# Micro_Grid_Sch.net
KiCad netlist of a schematic drawn in Altium Designer
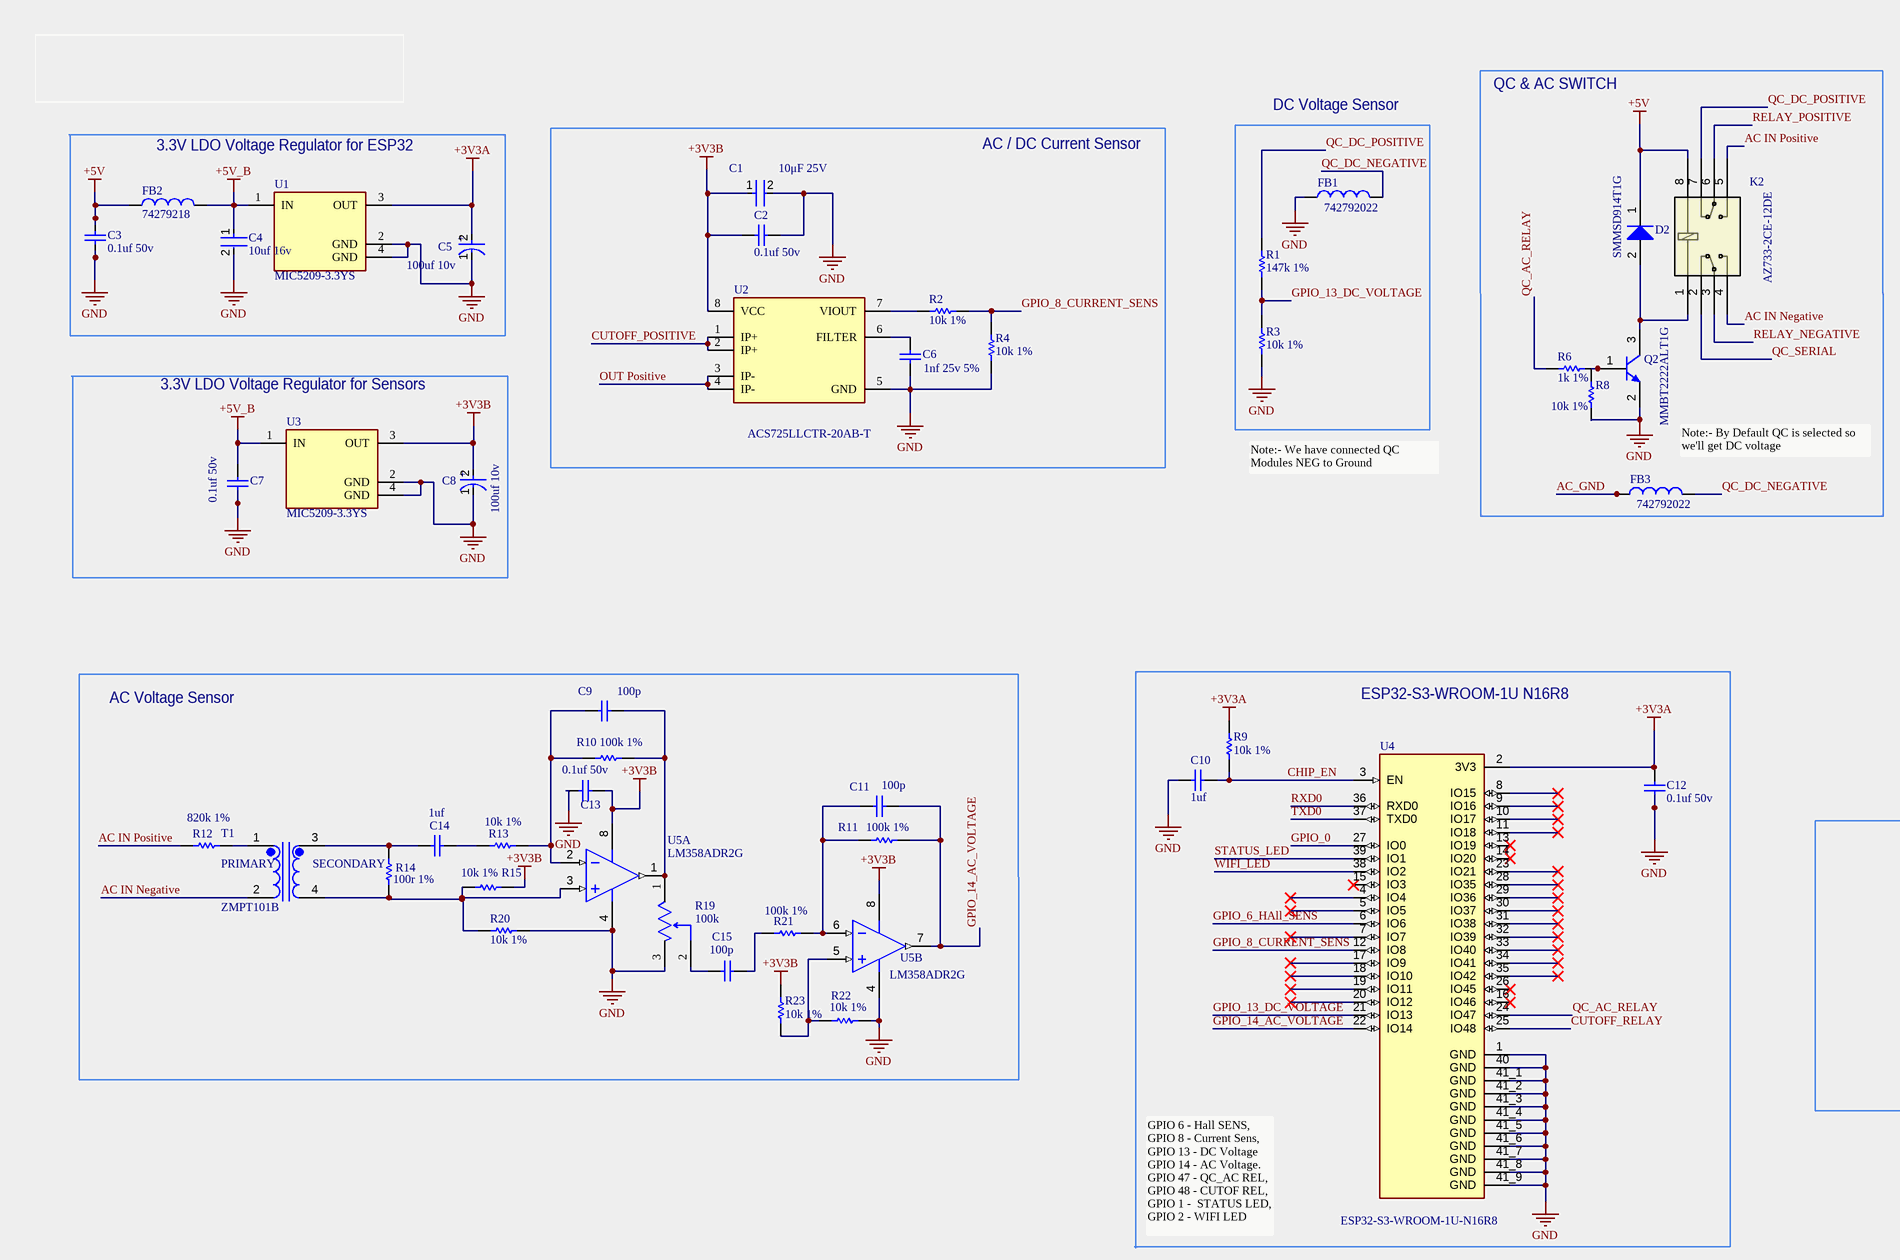
[diagram p0: Micro_Grid_Sch.SchDoc, top left]
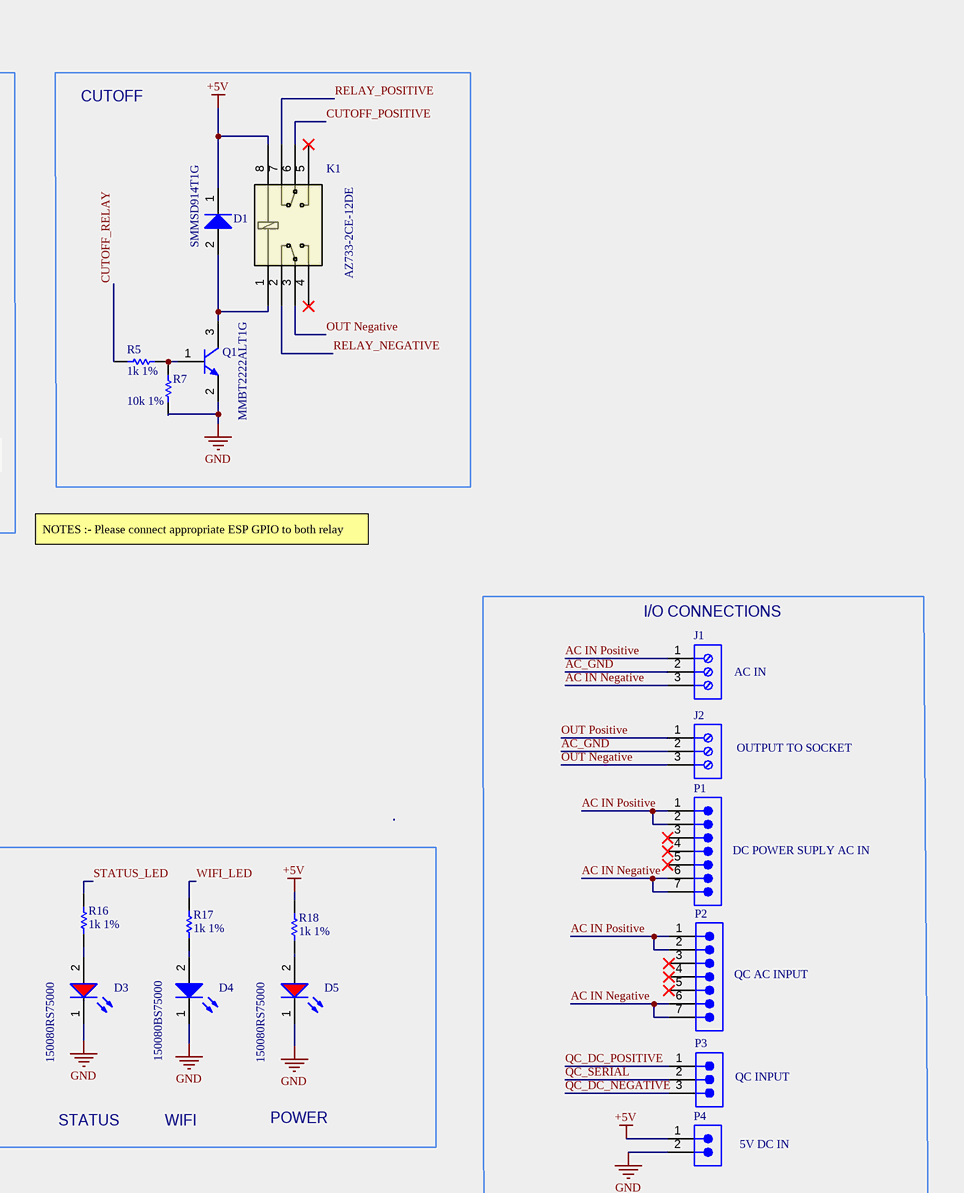
[diagram p1: Micro_Grid_Sch.SchDoc, top right]
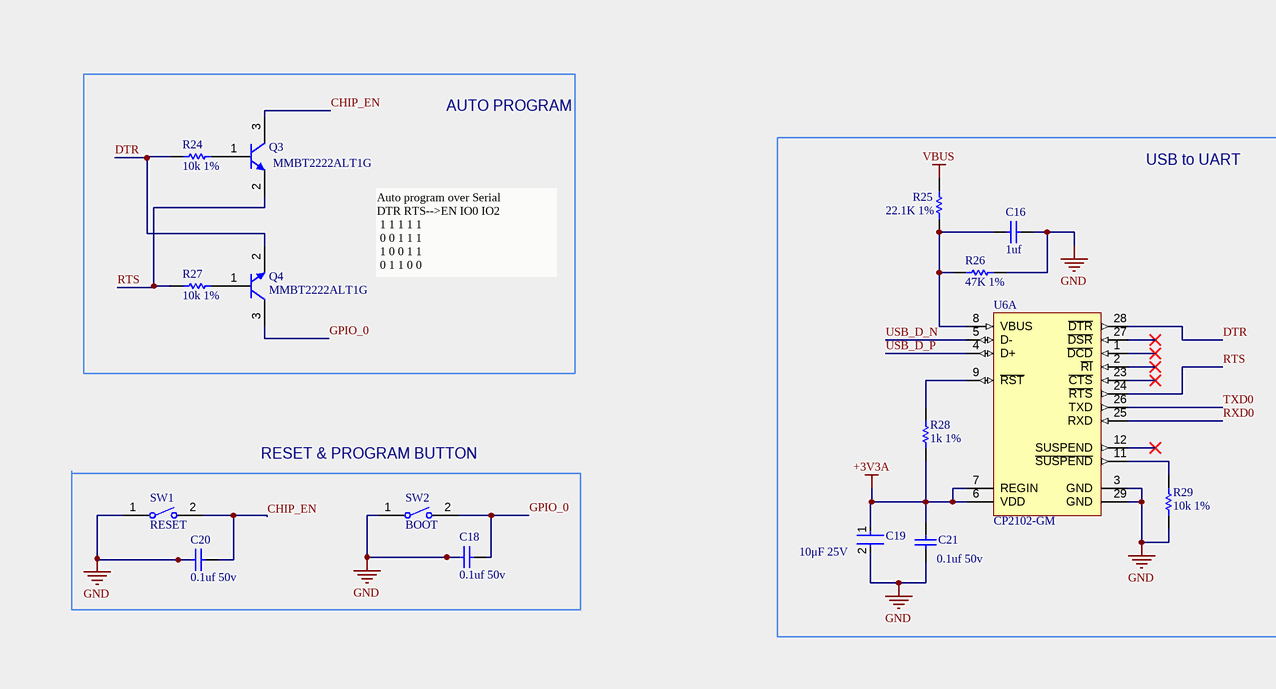
[diagram p2: Micro_Grid_Sch.SchDoc, bottom left]
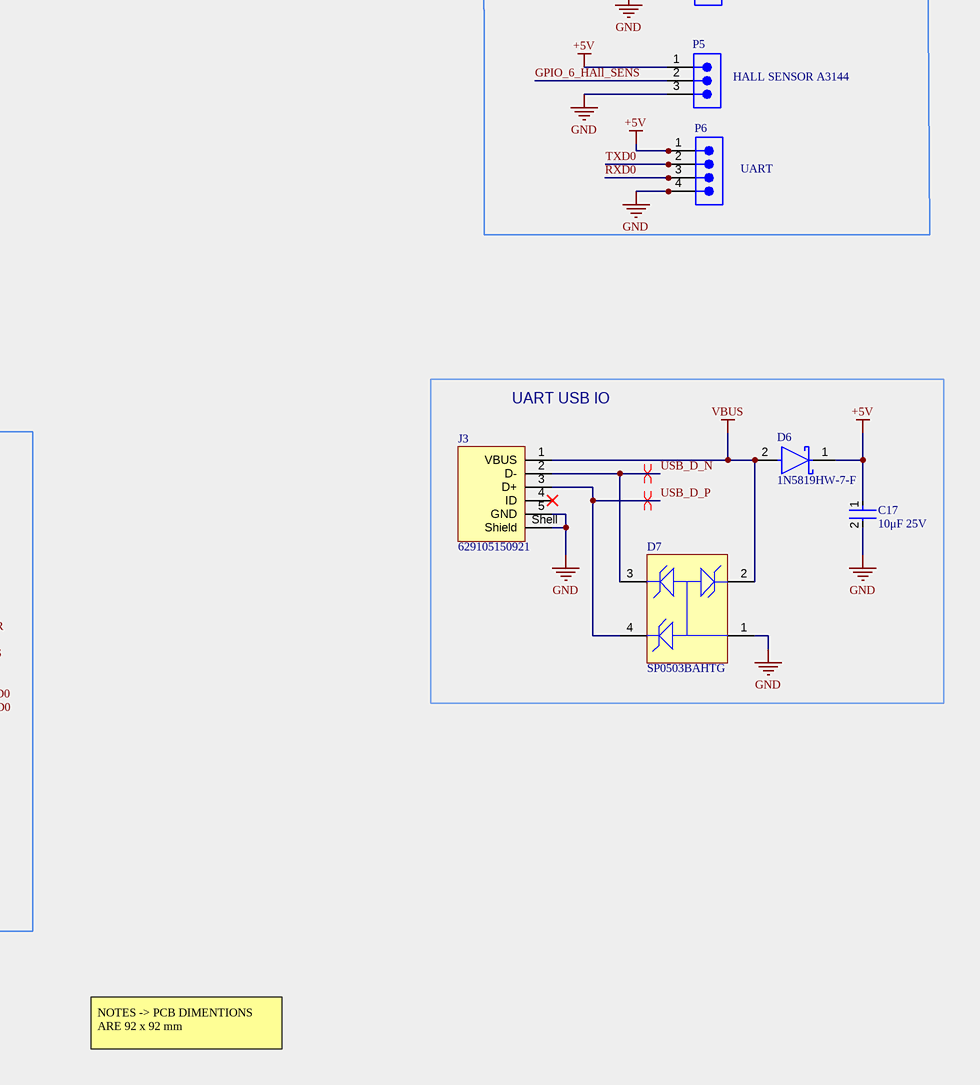
[diagram p3: Micro_Grid_Sch.SchDoc, bottom right]

(export (version "E")
  (design (tool "Eeschema 10.0.6"))
  (components
    (comp (ref "C1")
      (value "10μF 25V")
      (footprint "FP-C2012-125-0_2-IPC_B")
      (description "Multilayer Ceramic Capacitors 10μF ±10% 25V X5R SMD 0805")
      (fields (field (name "VOLTAGE") "25V") (field (name "TOLERANCE") "10%"))
      (libsource (lib "Altium Content Vault") (part "b4654b650e69147ec39a6b967a45e02"))
    )
    (comp (ref "C2")
      (value "0.1uf 50v")
      (footprint "CAPC2013X140X50LL20T25")
      (description "08055F104KAT2A")
      (fields (field (name "MANUFACTURER") "AVX Interconnect / Elco"))
      (libsource (lib "Altium Content Vault") (part "CAP"))
    )
    (comp (ref "C3")
      (value "0.1uf 50v")
      (footprint "CAPC2013X140X50LL20T25")
      (description "08055F104KAT2A")
      (fields (field (name "MANUFACTURER") "AVX Interconnect / Elco"))
      (libsource (lib "Altium Content Vault") (part "CAP"))
    )
    (comp (ref "C4")
      (value "10uf 16v")
      (footprint "FP-GRM21B-0_1-IPC_C")
      (description "Chip Multilayer Ceramic Capacitors for General Purpose, 0805, 10uF, X5R, 15%, 10%, 16V")
      (fields (field (name "TOLERANCE") "10%") (field (name "VOLTAGE") "16V"))
      (libsource (lib "Altium Content Vault") (part "b4654b650e69147ec39a6b967a45e02"))
    )
    (comp (ref "C5")
      (value "100uf 10v")
      (footprint "FP-SC-MFG")
      (description "EEE-1AA101WR, CAP ALUM 100UF 20% 10V SMD")
      (fields (field (name "TOLERANCE") "20%"))
      (libsource (lib "Altium Content Vault") (part "a00bbbee19879c290e62620ae7e47b1"))
    )
    (comp (ref "C6")
      (value "1nf 25v 5%")
      (footprint "CAPC2013X145X50NL20T20")
      (description "VJ0805Y102JXXPW1BC")
      (fields (field (name "MANUFACTURER") "Vitramon"))
      (libsource (lib "Altium Content Vault") (part "CAP"))
    )
    (comp (ref "C7")
      (value "0.1uf 50v")
      (footprint "CAPC2013X140X50LL20T25")
      (description "08055F104KAT2A")
      (fields (field (name "MANUFACTURER") "AVX Interconnect / Elco"))
      (libsource (lib "Altium Content Vault") (part "CAP"))
    )
    (comp (ref "C8")
      (value "100uf 10v")
      (footprint "FP-SC-MFG")
      (description "EEE-1AA101WR, CAP ALUM 100UF 20% 10V SMD")
      (fields (field (name "TOLERANCE") "20%"))
      (libsource (lib "Altium Content Vault") (part "a00bbbee19879c290e62620ae7e47b1"))
    )
    (comp (ref "C9")
      (value "100p")
      (footprint "CAPC2013X140X50NL20T25")
      (description "C0805C101KCGACTU")
      (fields (field (name "MANUFACTURER") "Kemet"))
      (libsource (lib "Altium Content Vault") (part "CAP"))
    )
    (comp (ref "C10")
      (value "1uf")
      (footprint "CAPC2013X140X50LL20T25")
      (description "C0805C105K3RACTU")
      (fields (field (name "MANUFACTURER") "Kemet"))
      (libsource (lib "Altium Content Vault") (part "CAP"))
    )
    (comp (ref "C11")
      (value "100p")
      (footprint "CAPC2013X140X50NL20T25")
      (description "C0805C101KCGACTU")
      (fields (field (name "MANUFACTURER") "Kemet"))
      (libsource (lib "Altium Content Vault") (part "CAP"))
    )
    (comp (ref "C12")
      (value "0.1uf 50v")
      (footprint "CAPC2013X140X50LL20T25")
      (description "08055F104KAT2A")
      (fields (field (name "MANUFACTURER") "AVX Interconnect / Elco"))
      (libsource (lib "Altium Content Vault") (part "CAP"))
    )
    (comp (ref "C13")
      (value "0.1uf 50v")
      (footprint "CAPC2013X140X50LL20T25")
      (description "08055F104KAT2A")
      (fields (field (name "MANUFACTURER") "AVX Interconnect / Elco"))
      (libsource (lib "Altium Content Vault") (part "CAP"))
    )
    (comp (ref "C14")
      (value "1uf")
      (footprint "CAPC2013X140X50LL20T25")
      (description "C0805C105K3RACTU")
      (fields (field (name "MANUFACTURER") "Kemet"))
      (libsource (lib "Altium Content Vault") (part "CAP"))
    )
    (comp (ref "C15")
      (value "100p")
      (footprint "CAPC2013X140X50NL20T25")
      (description "C0805C101KCGACTU")
      (fields (field (name "MANUFACTURER") "Kemet"))
      (libsource (lib "Altium Content Vault") (part "CAP"))
    )
    (comp (ref "C16")
      (value "1uf")
      (footprint "CAPC2013X140X50LL20T25")
      (description "C0805C105K3RACTU")
      (fields (field (name "MANUFACTURER") "Kemet"))
      (libsource (lib "Altium Content Vault") (part "CAP"))
    )
    (comp (ref "C17")
      (value "10μF 25V")
      (footprint "FP-C2012-125-0_2-IPC_B")
      (description "Multilayer Ceramic Capacitors 10μF ±10% 25V X5R SMD 0805")
      (fields (field (name "VOLTAGE") "25V") (field (name "TOLERANCE") "10%"))
      (libsource (lib "Altium Content Vault") (part "b4654b650e69147ec39a6b967a45e02"))
    )
    (comp (ref "C18")
      (value "0.1uf 50v")
      (footprint "CAPC2013X140X50LL20T25")
      (description "08055F104KAT2A")
      (fields (field (name "MANUFACTURER") "AVX Interconnect / Elco"))
      (libsource (lib "Altium Content Vault") (part "CAP"))
    )
    (comp (ref "C19")
      (value "10μF 25V")
      (footprint "FP-C2012-125-0_2-IPC_B")
      (description "Multilayer Ceramic Capacitors 10μF ±10% 25V X5R SMD 0805")
      (fields (field (name "VOLTAGE") "25V") (field (name "TOLERANCE") "10%"))
      (libsource (lib "Altium Content Vault") (part "b4654b650e69147ec39a6b967a45e02"))
    )
    (comp (ref "C20")
      (value "0.1uf 50v")
      (footprint "CAPC2013X140X50LL20T25")
      (description "08055F104KAT2A")
      (fields (field (name "MANUFACTURER") "AVX Interconnect / Elco"))
      (libsource (lib "Altium Content Vault") (part "CAP"))
    )
    (comp (ref "C21")
      (value "0.1uf 50v")
      (footprint "CAPC2013X140X50LL20T25")
      (description "08055F104KAT2A")
      (fields (field (name "MANUFACTURER") "AVX Interconnect / Elco"))
      (libsource (lib "Altium Content Vault") (part "CAP"))
    )
    (comp (ref "D1")
      (value "SMMSD914T1G")
      (footprint "ONSC-SOD-123-2-425-04_V")
      (description "SMMSD914T1G, Switching Diode, 2-Pin SOD-123, Pb-Free, Tape and Reel")
      (fields (field (name "MANUFACTURER") "On Semiconductor"))
      (libsource (lib "Altium Content Vault") (part "ONSC-D-K1A2-2"))
    )
    (comp (ref "D2")
      (value "SMMSD914T1G")
      (footprint "ONSC-SOD-123-2-425-04_V")
      (description "SMMSD914T1G, Switching Diode, 2-Pin SOD-123, Pb-Free, Tape and Reel")
      (fields (field (name "MANUFACTURER") "On Semiconductor"))
      (libsource (lib "Altium Content Vault") (part "ONSC-D-K1A2-2"))
    )
    (comp (ref "D3")
      (value "150080RS75000")
      (footprint "WL-SMCW_0805_150080xx75000")
      (description "LED Uni-Color Red 630nm 2-Pin Chip 0805(2012Metric) T/R")
      (libsource (lib "Altium Content Vault") (part "LED_Red_2A-1K"))
    )
    (comp (ref "D4")
      (value "150080BS75000")
      (footprint "WL-SMCW_0805_150080xx75000")
      (description "Led, Blue, 470 Nm, 3.2 V, 30 Ma, 145 Mcd Rohs Compliant: Yes")
      (libsource (lib "Altium Content Vault") (part "LED_Blue_2A-1K"))
    )
    (comp (ref "D5")
      (value "150080RS75000")
      (footprint "WL-SMCW_0805_150080xx75000")
      (description "LED Uni-Color Red 630nm 2-Pin Chip 0805(2012Metric) T/R")
      (libsource (lib "Altium Content Vault") (part "LED_Red_2A-1K"))
    )
    (comp (ref "D6")
      (value "1N5819HW-7-F")
      (footprint "FP-SOD123-IPC_A")
      (description "DIODE SCHOTTKY 40V 1A SOD123")
      (libsource (lib "Altium Content Vault") (part "1d6ec82d83fb6aee721767c19dac4b9"))
    )
    (comp (ref "D7")
      (value "SP0503BAHTG")
      (footprint "LFUS-SOT143-4_V")
      (description "TVS Diode Array, 30 pF, 30 KV, -40 to 85 degC, 4-Pin SOT143, RoHS, Tape and Reel")
      (fields (field (name "MANUFACTURER") "Littelfuse"))
      (libsource (lib "Altium Content Vault") (part "LFUS-SP0503BAHTG-SOT143-4"))
    )
    (comp (ref "FB1")
      (value "742792022")
      (footprint "WE-CBF_0805_L2W1.2H0.9_HC")
      (fields (field (name "TOLERANCE") "25%"))
      (libsource (lib "Altium Content Vault") (part "Ferrite"))
    )
    (comp (ref "FB2")
      (value "74279218")
      (footprint "WE-CBF_1206_L3.2W1.6H1.1_HC")
      (fields (field (name "TOLERANCE") "25%"))
      (libsource (lib "Altium Content Vault") (part "Ferrite"))
    )
    (comp (ref "FB3")
      (value "742792022")
      (footprint "WE-CBF_0805_L2W1.2H0.9_HC")
      (fields (field (name "TOLERANCE") "25%"))
      (libsource (lib "Altium Content Vault") (part "Ferrite"))
    )
    (comp (ref "J1")
      (value "AC IN")
      (footprint "691214110003")
      (fields (field (name "VOLTAGE") "300V"))
      (libsource (lib "Altium Content Vault") (part "TBL - 1R - 03P - Screw"))
    )
    (comp (ref "J2")
      (value "OUTPUT TO SOCKET")
      (footprint "691214110003")
      (fields (field (name "VOLTAGE") "300V"))
      (libsource (lib "Altium Content Vault") (part "TBL - 1R - 03P - Screw"))
    )
    (comp (ref "J3")
      (value "629105150921")
      (footprint "629105150921")
      (libsource (lib "Altium Content Vault") (part "Micro USB 2.0_Type AB_Receptacle_1 Port"))
    )
    (comp (ref "K1")
      (value "AZ733-2CE-12DE")
      (footprint "AZ733-2C_AMZ")
      (description "No Description Available")
      (libsource (lib "AZ733-2CE-12DE") (part "AZ733-2CE-12DE"))
    )
    (comp (ref "K2")
      (value "AZ733-2CE-12DE")
      (footprint "AZ733-2C_AMZ")
      (description "No Description Available")
      (libsource (lib "AZ733-2CE-12DE") (part "AZ733-2CE-12DE"))
    )
    (comp (ref "P1")
      (value "DC POWER SUPLY AC IN")
      (footprint "61300711121")
      (libsource (lib "Altium Content Vault") (part "Header_Male_1R_07P"))
    )
    (comp (ref "P2")
      (value "QC AC INPUT")
      (footprint "61300711121")
      (libsource (lib "Altium Content Vault") (part "Header_Male_1R_07P"))
    )
    (comp (ref "P3")
      (value "QC INPUT")
      (footprint "61300311121")
      (libsource (lib "Altium Content Vault") (part "Header_Male_1R_03P"))
    )
    (comp (ref "P4")
      (value "5V DC IN")
      (footprint "61300211121")
      (libsource (lib "Altium Content Vault") (part "Header_Male_1R_02P"))
    )
    (comp (ref "P5")
      (value "HALL SENSOR A3144")
      (footprint "61300311121")
      (libsource (lib "Altium Content Vault") (part "Header_Male_1R_03P"))
    )
    (comp (ref "P6")
      (value "UART")
      (footprint "61300411121")
      (libsource (lib "Altium Content Vault") (part "Header_Male_1R_04P"))
    )
    (comp (ref "Q1")
      (value "MMBT2222ALT1G")
      (footprint "ONSC-SOT-23-3-318-08_V")
      (description "General Purpose Transistor, NPN Silicon, 3-Pin SOT-23, Pb-Free, Tape and Reel")
      (fields (field (name "MANUFACTURER") "On Semiconductor"))
      (libsource (lib "Altium Content Vault") (part "ONSC-NPN-B1E2C3-3"))
    )
    (comp (ref "Q2")
      (value "MMBT2222ALT1G")
      (footprint "ONSC-SOT-23-3-318-08_V")
      (description "General Purpose Transistor, NPN Silicon, 3-Pin SOT-23, Pb-Free, Tape and Reel")
      (fields (field (name "MANUFACTURER") "On Semiconductor"))
      (libsource (lib "Altium Content Vault") (part "ONSC-NPN-B1E2C3-3"))
    )
    (comp (ref "Q3")
      (value "MMBT2222ALT1G")
      (footprint "ONSC-SOT-23-3-318-08_V")
      (description "General Purpose Transistor, NPN Silicon, 3-Pin SOT-23, Pb-Free, Tape and Reel")
      (fields (field (name "MANUFACTURER") "On Semiconductor"))
      (libsource (lib "Altium Content Vault") (part "ONSC-NPN-B1E2C3-3"))
    )
    (comp (ref "Q4")
      (value "MMBT2222ALT1G")
      (footprint "ONSC-SOT-23-3-318-08_V")
      (description "General Purpose Transistor, NPN Silicon, 3-Pin SOT-23, Pb-Free, Tape and Reel")
      (fields (field (name "MANUFACTURER") "On Semiconductor"))
      (libsource (lib "Altium Content Vault") (part "ONSC-NPN-B1E2C3-3"))
    )
    (comp (ref "R1")
      (value "147k 1%")
      (footprint "RESC2013X70X40LL20T20")
      (description "ERJ-6ENF1473V")
      (fields (field (name "MANUFACTURER") "Panasonic"))
      (libsource (lib "Altium Content Vault") (part "RES"))
    )
    (comp (ref "R2")
      (value "10k 1%")
      (footprint "RESC2013X50X30NL20T20")
      (fields (field (name "MANUFACTURER") "Vishay Dale") (field (name "PART NUMBER") "CRCW080510R0FKEA"))
      (libsource (lib "Altium Content Vault") (part "RES"))
    )
    (comp (ref "R3")
      (value "10k 1%")
      (footprint "RESC2013X60X40NL15T20")
      (description "CRCW080510K0FKEAHP")
      (fields (field (name "MANUFACTURER") "Vishay Dale"))
      (libsource (lib "Altium Content Vault") (part "RES"))
    )
    (comp (ref "R4")
      (value "10k 1%")
      (footprint "RESC2013X50X30NL20T20")
      (fields (field (name "MANUFACTURER") "Vishay Dale") (field (name "PART NUMBER") "CRCW080510R0FKEA"))
      (libsource (lib "Altium Content Vault") (part "RES"))
    )
    (comp (ref "R5")
      (value "1k 1%")
      (footprint "RESC2013X60X35ML10T20")
      (fields (field (name "TOLERANCE") "1%") (field (name "MANUFACTURER") "Yageo"))
      (libsource (lib "Altium Content Vault") (part "RES-2"))
    )
    (comp (ref "R6")
      (value "1k 1%")
      (footprint "RESC2013X60X35ML10T20")
      (fields (field (name "TOLERANCE") "1%") (field (name "MANUFACTURER") "Yageo"))
      (libsource (lib "Altium Content Vault") (part "RES-2"))
    )
    (comp (ref "R7")
      (value "10k 1%")
      (footprint "RESC2013X60X40NL15T20")
      (description "CRCW080510K0FKEAHP")
      (fields (field (name "MANUFACTURER") "Vishay Dale"))
      (libsource (lib "Altium Content Vault") (part "RES"))
    )
    (comp (ref "R8")
      (value "10k 1%")
      (footprint "RESC2013X60X40NL15T20")
      (description "CRCW080510K0FKEAHP")
      (fields (field (name "MANUFACTURER") "Vishay Dale"))
      (libsource (lib "Altium Content Vault") (part "RES"))
    )
    (comp (ref "R9")
      (value "10k 1%")
      (footprint "RESC2013X60X40NL15T20")
      (description "CRCW080510K0FKEAHP")
      (fields (field (name "MANUFACTURER") "Vishay Dale"))
      (libsource (lib "Altium Content Vault") (part "RES"))
    )
    (comp (ref "R10")
      (value "100k 1%")
      (footprint "RESC2013X60X30NL20T20")
      (description "RK73H2ATTD1003F")
      (fields (field (name "MANUFACTURER") "KOA Speer"))
      (libsource (lib "Altium Content Vault") (part "RES"))
    )
    (comp (ref "R11")
      (value "100k 1%")
      (footprint "RESC2013X60X30NL20T20")
      (description "RK73H2ATTD1003F")
      (fields (field (name "MANUFACTURER") "KOA Speer"))
      (libsource (lib "Altium Content Vault") (part "RES"))
    )
    (comp (ref "R12")
      (value "820k 1%")
      (footprint "RESC2013X70X40ML20T20")
      (description "ERJ6ENF8203V")
      (fields (field (name "MANUFACTURER") "Panasonic"))
      (libsource (lib "Altium Content Vault") (part "RES"))
    )
    (comp (ref "R13")
      (value "10k 1%")
      (footprint "RESC2013X60X40NL15T20")
      (description "CRCW080510K0FKEAHP")
      (fields (field (name "MANUFACTURER") "Vishay Dale"))
      (libsource (lib "Altium Content Vault") (part "RES"))
    )
    (comp (ref "R14")
      (value "100r 1%")
      (footprint "RESC2013X50X30LL20T20")
      (description "CRCW0805100RFKEA")
      (fields (field (name "MANUFACTURER") "Vishay Dale"))
      (libsource (lib "Altium Content Vault") (part "RES"))
    )
    (comp (ref "R15")
      (value "10k 1%")
      (footprint "RESC2013X60X40NL15T20")
      (description "CRCW080510K0FKEAHP")
      (fields (field (name "MANUFACTURER") "Vishay Dale"))
      (libsource (lib "Altium Content Vault") (part "RES"))
    )
    (comp (ref "R16")
      (value "1k 1%")
      (footprint "RESC2013X60X35ML10T20")
      (fields (field (name "TOLERANCE") "1%") (field (name "MANUFACTURER") "Yageo"))
      (libsource (lib "Altium Content Vault") (part "RES-2"))
    )
    (comp (ref "R17")
      (value "1k 1%")
      (footprint "RESC2013X60X35ML10T20")
      (fields (field (name "TOLERANCE") "1%") (field (name "MANUFACTURER") "Yageo"))
      (libsource (lib "Altium Content Vault") (part "RES-2"))
    )
    (comp (ref "R18")
      (value "1k 1%")
      (footprint "RESC2013X60X35ML10T20")
      (fields (field (name "TOLERANCE") "1%") (field (name "MANUFACTURER") "Yageo"))
      (libsource (lib "Altium Content Vault") (part "RES-2"))
    )
    (comp (ref "R19")
      (value "100k")
      (footprint "FP-TS53YL-MFG")
      (fields (field (name "TOLERANCE") "20%"))
      (libsource (lib "Altium Content Vault") (part "e21f4028687b11c314187cfd008b658"))
    )
    (comp (ref "R20")
      (value "10k 1%")
      (footprint "RESC2013X60X40NL15T20")
      (description "CRCW080510K0FKEAHP")
      (fields (field (name "MANUFACTURER") "Vishay Dale"))
      (libsource (lib "Altium Content Vault") (part "RES"))
    )
    (comp (ref "R21")
      (value "100k 1%")
      (footprint "RESC2013X60X30NL20T20")
      (description "RK73H2ATTD1003F")
      (fields (field (name "MANUFACTURER") "KOA Speer"))
      (libsource (lib "Altium Content Vault") (part "RES"))
    )
    (comp (ref "R22")
      (value "10k 1%")
      (footprint "RESC2013X60X40NL15T20")
      (description "CRCW080510K0FKEAHP")
      (fields (field (name "MANUFACTURER") "Vishay Dale"))
      (libsource (lib "Altium Content Vault") (part "RES"))
    )
    (comp (ref "R23")
      (value "10k 1%")
      (footprint "RESC2013X60X40NL15T20")
      (description "CRCW080510K0FKEAHP")
      (fields (field (name "MANUFACTURER") "Vishay Dale"))
      (libsource (lib "Altium Content Vault") (part "RES"))
    )
    (comp (ref "R24")
      (value "10k 1%")
      (footprint "RESC2013X60X40NL15T20")
      (description "CRCW080510K0FKEAHP")
      (fields (field (name "MANUFACTURER") "Vishay Dale"))
      (libsource (lib "Altium Content Vault") (part "RES"))
    )
    (comp (ref "R25")
      (value "22.1K 1%")
      (footprint "RESC2013X70X40NL20T20")
      (description "ERJ-6ENF2212V")
      (fields (field (name "MANUFACTURER") "Panasonic"))
      (libsource (lib "Altium Content Vault") (part "RES"))
    )
    (comp (ref "R26")
      (value "47K 1%")
      (footprint "RESC2013X60X35NL10T20")
      (fields (field (name "MANUFACTURER") "Yageo"))
      (libsource (lib "Altium Content Vault") (part "RES-2"))
    )
    (comp (ref "R27")
      (value "10k 1%")
      (footprint "RESC2013X60X40NL15T20")
      (description "CRCW080510K0FKEAHP")
      (fields (field (name "MANUFACTURER") "Vishay Dale"))
      (libsource (lib "Altium Content Vault") (part "RES"))
    )
    (comp (ref "R28")
      (value "1k 1%")
      (footprint "RESC2013X60X35ML10T20")
      (fields (field (name "TOLERANCE") "1%") (field (name "MANUFACTURER") "Yageo"))
      (libsource (lib "Altium Content Vault") (part "RES-2"))
    )
    (comp (ref "R29")
      (value "10k 1%")
      (footprint "RESC2013X60X35NL10T20")
      (fields (field (name "MANUFACTURER") "Yageo"))
      (libsource (lib "Altium Content Vault") (part "RES-2"))
    )
    (comp (ref "SW1")
      (value "RESET")
      (footprint "TECO-FSMSM-2_V")
      (description "FSMSM Push Button Switch, 50 mA, -35 to 85 degC, 2-Pin SMD, RoHS, Bulk")
      (fields (field (name "MANUFACTURER") "TE Connectivity"))
      (libsource (lib "Altium Content Vault") (part "SW-SPST-2_C"))
    )
    (comp (ref "SW2")
      (value "BOOT")
      (footprint "TECO-FSMSM-2_V")
      (description "FSMSM Push Button Switch, 50 mA, -35 to 85 degC, 2-Pin SMD, RoHS, Bulk")
      (fields (field (name "MANUFACTURER") "TE Connectivity"))
      (libsource (lib "Altium Content Vault") (part "SW-SPST-2_C"))
    )
    (comp (ref "T1")
      (value "ZMPT101B")
      (footprint "XFMR_ZMPT101B")
      (description "Current-type Voltage Transformer")
      (fields (field (name "MF") "Qingxian Zeming Langxi Electronic"))
      (libsource (lib "ZMPT101B") (part "ZMPT101B"))
    )
    (comp (ref "U1")
      (value "MIC5209-3.3YS")
      (footprint "FP-SOT223-3LD-PL-1-IPC_A")
      (description "IC REG LINEAR 3.3V 500MA SOT223")
      (libsource (lib "Altium Content Vault") (part "b06950a22b8c8924b346558efe1a73d"))
    )
    (comp (ref "U2")
      (value "ACS725LLCTR-20AB-T")
      (footprint "FP-LCN-8-IPC_B")
      (description "SENSOR CURRENT HALL 20A AC/DC")
      (libsource (lib "Altium Content Vault") (part "24c2fda9b8a0b4b902445efe0d7face"))
    )
    (comp (ref "U3")
      (value "MIC5209-3.3YS")
      (footprint "FP-SOT223-3LD-PL-1-IPC_A")
      (description "IC REG LINEAR 3.3V 500MA SOT223")
      (libsource (lib "Altium Content Vault") (part "b06950a22b8c8924b346558efe1a73d"))
    )
    (comp (ref "U4")
      (value "ESP32-S3-WROOM-1U-N16R8")
      (footprint "XCVR_ESP32-S3-WROOM-1U-N16R8")
      (fields (field (name "MF") "Espressif Systems"))
      (libsource (lib "ESP32-S3-WROOM-1U-N16R8") (part "ESP32-S3-WROOM-1U-N16R8"))
    )
    (comp (ref "U5")
      (value "LM358ADR2G")
      (footprint "ONSC-SOIC-8-751-07_V")
      (fields (field (name "MANUFACTURER") "On Semiconductor"))
      (libsource (lib "Altium Content Vault") (part "ONSC-LM358_NCV2904-8"))
    )
    (comp (ref "U6")
      (value "CP2102-GM")
      (footprint "SLAB-QFN-28-3125x3125TP_N")
      (description "Single-Chip USB to UART Bridge, 1024 Bytes EEPROM, -40 to 85 degC, 28-pin QFN, Tube")
      (fields (field (name "MANUFACTURER") "Silicon Labs"))
      (libsource (lib "Altium Content Vault") (part "SLAB-CP210X-QFN-28-29"))
    )
  )
  (nets
    (net (code "1") (name "+3V3A") (class "Default")
      (node (ref "C12") (pin "2") (pinfunction "2_2") (pintype "passive"))
      (node (ref "C19") (pin "1") (pinfunction "1_1") (pintype "passive"))
      (node (ref "C21") (pin "2") (pinfunction "2_2") (pintype "passive"))
      (node (ref "C5") (pin "2") (pinfunction "A_2") (pintype "passive"))
      (node (ref "R28") (pin "2") (pinfunction "2_2") (pintype "passive"))
      (node (ref "R9") (pin "1") (pinfunction "1_1") (pintype "passive"))
      (node (ref "U1") (pin "3") (pinfunction "OUT_3") (pintype "power_in"))
      (node (ref "U4") (pin "2") (pinfunction "3V3_2") (pintype "power_in"))
      (node (ref "U6") (pin "6") (pinfunction "VDD_6") (pintype "power_in"))
      (node (ref "U6") (pin "7") (pinfunction "REGIN_7") (pintype "power_in"))
    )
    (net (code "2") (name "+3V3B") (class "Default")
      (node (ref "C1") (pin "1") (pinfunction "1_1") (pintype "passive"))
      (node (ref "C13") (pin "1") (pinfunction "1_1") (pintype "passive"))
      (node (ref "C2") (pin "2") (pinfunction "2_2") (pintype "passive"))
      (node (ref "C8") (pin "2") (pinfunction "A_2") (pintype "passive"))
      (node (ref "R15") (pin "2") (pinfunction "2_2") (pintype "passive"))
      (node (ref "R23") (pin "2") (pinfunction "2_2") (pintype "passive"))
      (node (ref "U2") (pin "8") (pinfunction "VCC_8") (pintype "power_in"))
      (node (ref "U3") (pin "3") (pinfunction "OUT_3") (pintype "power_in"))
      (node (ref "U5") (pin "8") (pinfunction "VCC_8") (pintype "power_in"))
    )
    (net (code "3") (name "+5V") (class "Default")
      (node (ref "C17") (pin "1") (pinfunction "1_1") (pintype "passive"))
      (node (ref "C3") (pin "2") (pinfunction "2_2") (pintype "passive"))
      (node (ref "D1") (pin "1") (pinfunction "K_1") (pintype "passive"))
      (node (ref "D2") (pin "1") (pinfunction "K_1") (pintype "passive"))
      (node (ref "D6") (pin "1") (pinfunction "C_1") (pintype "passive"))
      (node (ref "FB2") (pin "1") (pinfunction "1_1") (pintype "passive"))
      (node (ref "K1") (pin "8") (pinfunction "8_8") (pintype "passive"))
      (node (ref "K2") (pin "8") (pinfunction "8_8") (pintype "passive"))
      (node (ref "P4") (pin "1") (pinfunction "1_1") (pintype "passive"))
      (node (ref "P5") (pin "1") (pinfunction "1_1") (pintype "passive"))
      (node (ref "P6") (pin "1") (pinfunction "1_1") (pintype "passive"))
      (node (ref "R18") (pin "1") (pinfunction "1_1") (pintype "passive"))
    )
    (net (code "4") (name "+5V_B") (class "Default")
      (node (ref "C4") (pin "1") (pinfunction "1_1") (pintype "passive"))
      (node (ref "C7") (pin "2") (pinfunction "2_2") (pintype "passive"))
      (node (ref "FB2") (pin "2") (pinfunction "2_2") (pintype "passive"))
      (node (ref "U1") (pin "1") (pinfunction "IN_1") (pintype "power_in"))
      (node (ref "U3") (pin "1") (pinfunction "IN_1") (pintype "power_in"))
    )
    (net (code "5") (name "/AC IN Negative") (class "Default")
      (node (ref "J1") (pin "3") (pinfunction "3_3") (pintype "passive"))
      (node (ref "K2") (pin "4") (pinfunction "4_4") (pintype "passive"))
      (node (ref "P1") (pin "6") (pinfunction "6_6") (pintype "passive"))
      (node (ref "P1") (pin "7") (pinfunction "7_7") (pintype "passive"))
      (node (ref "P2") (pin "6") (pinfunction "6_6") (pintype "passive"))
      (node (ref "P2") (pin "7") (pinfunction "7_7") (pintype "passive"))
      (node (ref "T1") (pin "2") (pinfunction "2_2") (pintype "passive"))
    )
    (net (code "6") (name "/AC IN Positive") (class "Default")
      (node (ref "J1") (pin "1") (pinfunction "1_1") (pintype "passive"))
      (node (ref "K2") (pin "5") (pinfunction "5_5") (pintype "passive"))
      (node (ref "P1") (pin "1") (pinfunction "1_1") (pintype "passive"))
      (node (ref "P1") (pin "2") (pinfunction "2_2") (pintype "passive"))
      (node (ref "P2") (pin "1") (pinfunction "1_1") (pintype "passive"))
      (node (ref "P2") (pin "2") (pinfunction "2_2") (pintype "passive"))
      (node (ref "R12") (pin "1") (pinfunction "1_1") (pintype "passive"))
    )
    (net (code "7") (name "/AC_GND") (class "Default")
      (node (ref "FB3") (pin "1") (pinfunction "1_1") (pintype "passive"))
      (node (ref "J1") (pin "2") (pinfunction "2_2") (pintype "passive"))
      (node (ref "J2") (pin "2") (pinfunction "2_2") (pintype "passive"))
    )
    (net (code "8") (name "/CHIP_EN") (class "Default")
      (node (ref "C10") (pin "2") (pinfunction "2_2") (pintype "passive"))
      (node (ref "C20") (pin "1") (pinfunction "1_1") (pintype "passive"))
      (node (ref "Q3") (pin "3") (pinfunction "C_3") (pintype "passive"))
      (node (ref "R9") (pin "2") (pinfunction "2_2") (pintype "passive"))
      (node (ref "SW1") (pin "2") (pinfunction "2_2") (pintype "passive"))
      (node (ref "U4") (pin "3") (pinfunction "EN_3") (pintype "input"))
    )
    (net (code "9") (name "/CUTOFF_POSITIVE") (class "Default")
      (node (ref "K1") (pin "6") (pinfunction "6_6") (pintype "passive"))
      (node (ref "U2") (pin "1") (pinfunction "IP+_1") (pintype "passive"))
      (node (ref "U2") (pin "2") (pinfunction "IP+_2") (pintype "passive"))
    )
    (net (code "10") (name "/CUTOFF_RELAY") (class "Default")
      (node (ref "R5") (pin "1") (pinfunction "1_1") (pintype "passive"))
      (node (ref "U4") (pin "25") (pinfunction "IO48_25") (pintype "bidirectional"))
    )
    (net (code "11") (name "/DTR") (class "Default")
      (node (ref "Q4") (pin "2") (pinfunction "E_2") (pintype "passive"))
      (node (ref "R24") (pin "2") (pinfunction "2_2") (pintype "passive"))
      (node (ref "U6") (pin "28") (pinfunction "~{DTR}_28") (pintype "output"))
    )
    (net (code "12") (name "/GPIO_0") (class "Default")
      (node (ref "C18") (pin "1") (pinfunction "1_1") (pintype "passive"))
      (node (ref "Q4") (pin "3") (pinfunction "C_3") (pintype "passive"))
      (node (ref "SW2") (pin "2") (pinfunction "2_2") (pintype "passive"))
      (node (ref "U4") (pin "27") (pinfunction "IO0_27") (pintype "bidirectional"))
    )
    (net (code "13") (name "/GPIO_6_HAll_SENS") (class "Default")
      (node (ref "P5") (pin "2") (pinfunction "2_2") (pintype "passive"))
      (node (ref "U4") (pin "6") (pinfunction "IO6_6") (pintype "bidirectional"))
    )
    (net (code "14") (name "/GPIO_8_CURRENT_SENS") (class "Default")
      (node (ref "R2") (pin "2") (pinfunction "2_2") (pintype "passive"))
      (node (ref "R4") (pin "2") (pinfunction "2_2") (pintype "passive"))
      (node (ref "U4") (pin "12") (pinfunction "IO8_12") (pintype "bidirectional"))
    )
    (net (code "15") (name "/GPIO_13_DC_VOLTAGE") (class "Default")
      (node (ref "R1") (pin "2") (pinfunction "2_2") (pintype "passive"))
      (node (ref "R3") (pin "1") (pinfunction "1_1") (pintype "passive"))
      (node (ref "U4") (pin "21") (pinfunction "IO13_21") (pintype "bidirectional"))
    )
    (net (code "16") (name "/GPIO_14_AC_VOLTAGE") (class "Default")
      (node (ref "C11") (pin "2") (pinfunction "2_2") (pintype "passive"))
      (node (ref "R11") (pin "2") (pinfunction "2_2") (pintype "passive"))
      (node (ref "U4") (pin "22") (pinfunction "IO14_22") (pintype "bidirectional"))
      (node (ref "U5") (pin "7") (pinfunction "OUTB_7") (pintype "output"))
    )
    (net (code "17") (name "/OUT Negative") (class "Default")
      (node (ref "J2") (pin "3") (pinfunction "3_3") (pintype "passive"))
      (node (ref "K1") (pin "3") (pinfunction "3_3") (pintype "passive"))
    )
    (net (code "18") (name "/OUT Positive") (class "Default")
      (node (ref "J2") (pin "1") (pinfunction "1_1") (pintype "passive"))
      (node (ref "U2") (pin "3") (pinfunction "IP-_3") (pintype "passive"))
      (node (ref "U2") (pin "4") (pinfunction "IP-_4") (pintype "passive"))
    )
    (net (code "19") (name "/QC_AC_RELAY") (class "Default")
      (node (ref "R6") (pin "1") (pinfunction "1_1") (pintype "passive"))
      (node (ref "U4") (pin "24") (pinfunction "IO47_24") (pintype "bidirectional"))
    )
    (net (code "20") (name "/QC_DC_NEGATIVE") (class "Default")
      (node (ref "FB1") (pin "2") (pinfunction "2_2") (pintype "passive"))
      (node (ref "FB3") (pin "2") (pinfunction "2_2") (pintype "passive"))
      (node (ref "P3") (pin "3") (pinfunction "3_3") (pintype "passive"))
    )
    (net (code "21") (name "/QC_DC_POSITIVE") (class "Default")
      (node (ref "K2") (pin "7") (pinfunction "7_7") (pintype "passive"))
      (node (ref "P3") (pin "1") (pinfunction "1_1") (pintype "passive"))
      (node (ref "R1") (pin "1") (pinfunction "1_1") (pintype "passive"))
    )
    (net (code "22") (name "/QC_SERIAL") (class "Default")
      (node (ref "K2") (pin "2") (pinfunction "2_2") (pintype "passive"))
      (node (ref "P3") (pin "2") (pinfunction "2_2") (pintype "passive"))
    )
    (net (code "23") (name "/RELAY_NEGATIVE") (class "Default")
      (node (ref "K1") (pin "2") (pinfunction "2_2") (pintype "passive"))
      (node (ref "K2") (pin "3") (pinfunction "3_3") (pintype "passive"))
    )
    (net (code "24") (name "/RELAY_POSITIVE") (class "Default")
      (node (ref "K1") (pin "7") (pinfunction "7_7") (pintype "passive"))
      (node (ref "K2") (pin "6") (pinfunction "6_6") (pintype "passive"))
    )
    (net (code "25") (name "/RTS") (class "Default")
      (node (ref "Q3") (pin "2") (pinfunction "E_2") (pintype "passive"))
      (node (ref "R27") (pin "2") (pinfunction "2_2") (pintype "passive"))
      (node (ref "U6") (pin "24") (pinfunction "~{RTS}_24") (pintype "output"))
    )
    (net (code "26") (name "/RXD0") (class "Default")
      (node (ref "P6") (pin "3") (pinfunction "3_3") (pintype "passive"))
      (node (ref "U4") (pin "36") (pinfunction "RXD0_36") (pintype "bidirectional"))
      (node (ref "U6") (pin "25") (pinfunction "RXD_25") (pintype "input"))
    )
    (net (code "27") (name "/STATUS_LED") (class "Default")
      (node (ref "R16") (pin "1") (pinfunction "1_1") (pintype "passive"))
      (node (ref "U4") (pin "39") (pinfunction "IO1_39") (pintype "bidirectional"))
    )
    (net (code "28") (name "/TXD0") (class "Default")
      (node (ref "P6") (pin "2") (pinfunction "2_2") (pintype "passive"))
      (node (ref "U4") (pin "37") (pinfunction "TXD0_37") (pintype "bidirectional"))
      (node (ref "U6") (pin "26") (pinfunction "TXD_26") (pintype "output"))
    )
    (net (code "29") (name "/USB_D_N") (class "Default")
      (node (ref "D7") (pin "3") (pinfunction "3_3") (pintype "passive"))
      (node (ref "J3") (pin "2") (pinfunction "D-_2") (pintype "passive"))
      (node (ref "U6") (pin "5") (pinfunction "D-_5") (pintype "bidirectional"))
    )
    (net (code "30") (name "/USB_D_P") (class "Default")
      (node (ref "D7") (pin "4") (pinfunction "4_4") (pintype "passive"))
      (node (ref "J3") (pin "3") (pinfunction "D+_3") (pintype "passive"))
      (node (ref "U6") (pin "4") (pinfunction "D+_4") (pintype "bidirectional"))
    )
    (net (code "31") (name "/WIFI_LED") (class "Default")
      (node (ref "R17") (pin "1") (pinfunction "1_1") (pintype "passive"))
      (node (ref "U4") (pin "38") (pinfunction "IO2_38") (pintype "bidirectional"))
    )
    (net (code "32") (name "GND") (class "Default")
      (node (ref "C1") (pin "2") (pinfunction "2_2") (pintype "passive"))
      (node (ref "C10") (pin "1") (pinfunction "1_1") (pintype "passive"))
      (node (ref "C12") (pin "1") (pinfunction "1_1") (pintype "passive"))
      (node (ref "C13") (pin "2") (pinfunction "2_2") (pintype "passive"))
      (node (ref "C16") (pin "2") (pinfunction "2_2") (pintype "passive"))
      (node (ref "C17") (pin "2") (pinfunction "2_2") (pintype "passive"))
      (node (ref "C18") (pin "2") (pinfunction "2_2") (pintype "passive"))
      (node (ref "C19") (pin "2") (pinfunction "2_2") (pintype "passive"))
      (node (ref "C2") (pin "1") (pinfunction "1_1") (pintype "passive"))
      (node (ref "C20") (pin "2") (pinfunction "2_2") (pintype "passive"))
      (node (ref "C21") (pin "1") (pinfunction "1_1") (pintype "passive"))
      (node (ref "C3") (pin "1") (pinfunction "1_1") (pintype "passive"))
      (node (ref "C4") (pin "2") (pinfunction "2_2") (pintype "passive"))
      (node (ref "C5") (pin "1") (pinfunction "C_1") (pintype "passive"))
      (node (ref "C6") (pin "2") (pinfunction "2_2") (pintype "passive"))
      (node (ref "C7") (pin "1") (pinfunction "1_1") (pintype "passive"))
      (node (ref "C8") (pin "1") (pinfunction "C_1") (pintype "passive"))
      (node (ref "D3") (pin "1") (pinfunction "K_1") (pintype "passive"))
      (node (ref "D4") (pin "1") (pinfunction "K_1") (pintype "passive"))
      (node (ref "D5") (pin "1") (pinfunction "K_1") (pintype "passive"))
      (node (ref "D7") (pin "1") (pinfunction "1_1") (pintype "passive"))
      (node (ref "FB1") (pin "1") (pinfunction "1_1") (pintype "passive"))
      (node (ref "J3") (pin "5") (pinfunction "GND_5") (pintype "passive"))
      (node (ref "J3") (pin "Shell") (pinfunction "Shield_Shell") (pintype "passive"))
      (node (ref "P4") (pin "2") (pinfunction "2_2") (pintype "passive"))
      (node (ref "P5") (pin "3") (pinfunction "3_3") (pintype "passive"))
      (node (ref "P6") (pin "4") (pinfunction "4_4") (pintype "passive"))
      (node (ref "Q1") (pin "2") (pinfunction "E_2") (pintype "passive"))
      (node (ref "Q2") (pin "2") (pinfunction "E_2") (pintype "passive"))
      (node (ref "R19") (pin "3") (pinfunction "c_3") (pintype "passive"))
      (node (ref "R20") (pin "2") (pinfunction "2_2") (pintype "passive"))
      (node (ref "R22") (pin "2") (pinfunction "2_2") (pintype "passive"))
      (node (ref "R26") (pin "2") (pinfunction "2_2") (pintype "passive"))
      (node (ref "R29") (pin "1") (pinfunction "1_1") (pintype "passive"))
      (node (ref "R3") (pin "2") (pinfunction "2_2") (pintype "passive"))
      (node (ref "R4") (pin "1") (pinfunction "1_1") (pintype "passive"))
      (node (ref "R7") (pin "1") (pinfunction "1_1") (pintype "passive"))
      (node (ref "R8") (pin "1") (pinfunction "1_1") (pintype "passive"))
      (node (ref "SW1") (pin "1") (pinfunction "1_1") (pintype "passive"))
      (node (ref "SW2") (pin "1") (pinfunction "1_1") (pintype "passive"))
      (node (ref "U1") (pin "2") (pinfunction "GND_2") (pintype "power_in"))
      (node (ref "U1") (pin "4") (pinfunction "GND_4") (pintype "power_in"))
      (node (ref "U2") (pin "5") (pinfunction "GND_5") (pintype "power_in"))
      (node (ref "U3") (pin "2") (pinfunction "GND_2") (pintype "power_in"))
      (node (ref "U3") (pin "4") (pinfunction "GND_4") (pintype "power_in"))
      (node (ref "U4") (pin "1") (pinfunction "GND_1") (pintype "power_in"))
      (node (ref "U4") (pin "40") (pinfunction "GND_40") (pintype "power_in"))
      (node (ref "U4") (pin "41_1") (pinfunction "GND_41_1") (pintype "power_in"))
      (node (ref "U4") (pin "41_2") (pinfunction "GND_41_2") (pintype "power_in"))
      (node (ref "U4") (pin "41_3") (pinfunction "GND_41_3") (pintype "power_in"))
      (node (ref "U4") (pin "41_4") (pinfunction "GND_41_4") (pintype "power_in"))
      (node (ref "U4") (pin "41_5") (pinfunction "GND_41_5") (pintype "power_in"))
      (node (ref "U4") (pin "41_6") (pinfunction "GND_41_6") (pintype "power_in"))
      (node (ref "U4") (pin "41_7") (pinfunction "GND_41_7") (pintype "power_in"))
      (node (ref "U4") (pin "41_8") (pinfunction "GND_41_8") (pintype "power_in"))
      (node (ref "U4") (pin "41_9") (pinfunction "GND_41_9") (pintype "power_in"))
      (node (ref "U5") (pin "4") (pinfunction "VEE/GND_4") (pintype "power_in"))
      (node (ref "U6") (pin "29") (pinfunction "GND_29") (pintype "power_in"))
      (node (ref "U6") (pin "3") (pinfunction "GND_3") (pintype "power_in"))
    )
    (net (code "33") (name "Net-(C14-Pad1)") (class "Default")
      (node (ref "C14") (pin "1") (pinfunction "1_1") (pintype "passive"))
      (node (ref "R14") (pin "2") (pinfunction "2_2") (pintype "passive"))
      (node (ref "T1") (pin "3") (pinfunction "3_3") (pintype "passive"))
    )
    (net (code "34") (name "Net-(C14-Pad2)") (class "Default")
      (node (ref "C14") (pin "2") (pinfunction "2_2") (pintype "passive"))
      (node (ref "R13") (pin "1") (pinfunction "1_1") (pintype "passive"))
    )
    (net (code "35") (name "Net-(C15-Pad2)") (class "Default")
      (node (ref "C15") (pin "2") (pinfunction "2_2") (pintype "passive"))
      (node (ref "R21") (pin "1") (pinfunction "1_1") (pintype "passive"))
    )
    (net (code "36") (name "Net-(D1-A)") (class "Default")
      (node (ref "D1") (pin "2") (pinfunction "A_2") (pintype "passive"))
      (node (ref "K1") (pin "1") (pinfunction "1_1") (pintype "passive"))
      (node (ref "Q1") (pin "3") (pinfunction "C_3") (pintype "passive"))
    )
    (net (code "37") (name "Net-(D2-A)") (class "Default")
      (node (ref "D2") (pin "2") (pinfunction "A_2") (pintype "passive"))
      (node (ref "K2") (pin "1") (pinfunction "1_1") (pintype "passive"))
      (node (ref "Q2") (pin "3") (pinfunction "C_3") (pintype "passive"))
    )
    (net (code "38") (name "Net-(D3-A)") (class "Default")
      (node (ref "D3") (pin "2") (pinfunction "A_2") (pintype "passive"))
      (node (ref "R16") (pin "2") (pinfunction "2_2") (pintype "passive"))
    )
    (net (code "39") (name "Net-(D4-A)") (class "Default")
      (node (ref "D4") (pin "2") (pinfunction "A_2") (pintype "passive"))
      (node (ref "R17") (pin "2") (pinfunction "2_2") (pintype "passive"))
    )
    (net (code "40") (name "Net-(D5-A)") (class "Default")
      (node (ref "D5") (pin "2") (pinfunction "A_2") (pintype "passive"))
      (node (ref "R18") (pin "2") (pinfunction "2_2") (pintype "passive"))
    )
    (net (code "41") (name "Net-(Q1-B)") (class "Default")
      (node (ref "Q1") (pin "1") (pinfunction "B_1") (pintype "passive"))
      (node (ref "R5") (pin "2") (pinfunction "2_2") (pintype "passive"))
      (node (ref "R7") (pin "2") (pinfunction "2_2") (pintype "passive"))
    )
    (net (code "42") (name "Net-(Q2-B)") (class "Default")
      (node (ref "Q2") (pin "1") (pinfunction "B_1") (pintype "passive"))
      (node (ref "R6") (pin "2") (pinfunction "2_2") (pintype "passive"))
      (node (ref "R8") (pin "2") (pinfunction "2_2") (pintype "passive"))
    )
    (net (code "43") (name "Net-(Q3-B)") (class "Default")
      (node (ref "Q3") (pin "1") (pinfunction "B_1") (pintype "passive"))
      (node (ref "R24") (pin "1") (pinfunction "1_1") (pintype "passive"))
    )
    (net (code "44") (name "Net-(Q4-B)") (class "Default")
      (node (ref "Q4") (pin "1") (pinfunction "B_1") (pintype "passive"))
      (node (ref "R27") (pin "1") (pinfunction "1_1") (pintype "passive"))
    )
    (net (code "45") (name "Net-(R12-Pad2)") (class "Default")
      (node (ref "R12") (pin "2") (pinfunction "2_2") (pintype "passive"))
      (node (ref "T1") (pin "1") (pinfunction "1_1") (pintype "passive"))
    )
    (net (code "46") (name "Net-(R19-a)") (class "Default")
      (node (ref "C9") (pin "2") (pinfunction "2_2") (pintype "passive"))
      (node (ref "R10") (pin "2") (pinfunction "2_2") (pintype "passive"))
      (node (ref "R19") (pin "1") (pinfunction "a_1") (pintype "passive"))
      (node (ref "U5") (pin "1") (pinfunction "OUTA_1") (pintype "output"))
    )
    (net (code "47") (name "Net-(R19-b)") (class "Default")
      (node (ref "C15") (pin "1") (pinfunction "1_1") (pintype "passive"))
      (node (ref "R19") (pin "2") (pinfunction "b_2") (pintype "passive"))
    )
    (net (code "48") (name "Net-(U2-FILTER)") (class "Default")
      (node (ref "C6") (pin "1") (pinfunction "1_1") (pintype "passive"))
      (node (ref "U2") (pin "6") (pinfunction "FILTER_6") (pintype "passive"))
    )
    (net (code "49") (name "Net-(U2-VIOUT)") (class "Default")
      (node (ref "R2") (pin "1") (pinfunction "1_1") (pintype "passive"))
      (node (ref "U2") (pin "7") (pinfunction "VIOUT_7") (pintype "passive"))
    )
    (net (code "50") (name "Net-(U5A-INA+)") (class "Default")
      (node (ref "R14") (pin "1") (pinfunction "1_1") (pintype "passive"))
      (node (ref "R15") (pin "1") (pinfunction "1_1") (pintype "passive"))
      (node (ref "R20") (pin "1") (pinfunction "1_1") (pintype "passive"))
      (node (ref "T1") (pin "4") (pinfunction "4_4") (pintype "passive"))
      (node (ref "U5") (pin "3") (pinfunction "INA+_3") (pintype "input"))
    )
    (net (code "51") (name "Net-(U5A-INA-)") (class "Default")
      (node (ref "C9") (pin "1") (pinfunction "1_1") (pintype "passive"))
      (node (ref "R10") (pin "1") (pinfunction "1_1") (pintype "passive"))
      (node (ref "R13") (pin "2") (pinfunction "2_2") (pintype "passive"))
      (node (ref "U5") (pin "2") (pinfunction "INA-_2") (pintype "input"))
    )
    (net (code "52") (name "Net-(U5B-INB+)") (class "Default")
      (node (ref "R22") (pin "1") (pinfunction "1_1") (pintype "passive"))
      (node (ref "R23") (pin "1") (pinfunction "1_1") (pintype "passive"))
      (node (ref "U5") (pin "5") (pinfunction "INB+_5") (pintype "input"))
    )
    (net (code "53") (name "Net-(U5B-INB-)") (class "Default")
      (node (ref "C11") (pin "1") (pinfunction "1_1") (pintype "passive"))
      (node (ref "R11") (pin "1") (pinfunction "1_1") (pintype "passive"))
      (node (ref "R21") (pin "2") (pinfunction "2_2") (pintype "passive"))
      (node (ref "U5") (pin "6") (pinfunction "INB-_6") (pintype "input"))
    )
    (net (code "54") (name "Net-(U6A-VBUS)") (class "Default")
      (node (ref "C16") (pin "1") (pinfunction "1_1") (pintype "passive"))
      (node (ref "R25") (pin "1") (pinfunction "1_1") (pintype "passive"))
      (node (ref "R26") (pin "1") (pinfunction "1_1") (pintype "passive"))
      (node (ref "U6") (pin "8") (pinfunction "VBUS_8") (pintype "input"))
    )
    (net (code "55") (name "Net-(U6A-~{RST})") (class "Default")
      (node (ref "R28") (pin "1") (pinfunction "1_1") (pintype "passive"))
      (node (ref "U6") (pin "9") (pinfunction "~{RST}_9") (pintype "bidirectional"))
    )
    (net (code "56") (name "Net-(U6A-~{SUSPEND})") (class "Default")
      (node (ref "R29") (pin "2") (pinfunction "2_2") (pintype "passive"))
      (node (ref "U6") (pin "11") (pinfunction "~{SUSPEND}_11") (pintype "output"))
    )
    (net (code "57") (name "VBUS") (class "Default")
      (node (ref "D6") (pin "2") (pinfunction "A_2") (pintype "passive"))
      (node (ref "D7") (pin "2") (pinfunction "2_2") (pintype "passive"))
      (node (ref "J3") (pin "1") (pinfunction "VBUS_1") (pintype "passive"))
      (node (ref "R25") (pin "2") (pinfunction "2_2") (pintype "passive"))
    )
    (net (code "58") (name "unconnected-(J3-ID-Pad4)") (class "Default")
      (node (ref "J3") (pin "4") (pinfunction "ID_4") (pintype "passive+no_connect"))
    )
    (net (code "59") (name "unconnected-(K1-Pad4)") (class "Default")
      (node (ref "K1") (pin "4") (pinfunction "4_4") (pintype "passive+no_connect"))
    )
    (net (code "60") (name "unconnected-(K1-Pad5)") (class "Default")
      (node (ref "K1") (pin "5") (pinfunction "5_5") (pintype "passive+no_connect"))
    )
    (net (code "61") (name "unconnected-(P1-Pad3)") (class "Default")
      (node (ref "P1") (pin "3") (pinfunction "3_3") (pintype "passive+no_connect"))
    )
    (net (code "62") (name "unconnected-(P1-Pad4)") (class "Default")
      (node (ref "P1") (pin "4") (pinfunction "4_4") (pintype "passive+no_connect"))
    )
    (net (code "63") (name "unconnected-(P1-Pad5)") (class "Default")
      (node (ref "P1") (pin "5") (pinfunction "5_5") (pintype "passive+no_connect"))
    )
    (net (code "64") (name "unconnected-(P2-Pad3)") (class "Default")
      (node (ref "P2") (pin "3") (pinfunction "3_3") (pintype "passive+no_connect"))
    )
    (net (code "65") (name "unconnected-(P2-Pad4)") (class "Default")
      (node (ref "P2") (pin "4") (pinfunction "4_4") (pintype "passive+no_connect"))
    )
    (net (code "66") (name "unconnected-(P2-Pad5)") (class "Default")
      (node (ref "P2") (pin "5") (pinfunction "5_5") (pintype "passive+no_connect"))
    )
    (net (code "67") (name "unconnected-(U4-IO3-Pad15)") (class "Default")
      (node (ref "U4") (pin "15") (pinfunction "IO3_15") (pintype "bidirectional+no_connect"))
    )
    (net (code "68") (name "unconnected-(U4-IO4-Pad4)") (class "Default")
      (node (ref "U4") (pin "4") (pinfunction "IO4_4") (pintype "bidirectional+no_connect"))
    )
    (net (code "69") (name "unconnected-(U4-IO5-Pad5)") (class "Default")
      (node (ref "U4") (pin "5") (pinfunction "IO5_5") (pintype "bidirectional+no_connect"))
    )
    (net (code "70") (name "unconnected-(U4-IO7-Pad7)") (class "Default")
      (node (ref "U4") (pin "7") (pinfunction "IO7_7") (pintype "bidirectional+no_connect"))
    )
    (net (code "71") (name "unconnected-(U4-IO9-Pad17)") (class "Default")
      (node (ref "U4") (pin "17") (pinfunction "IO9_17") (pintype "bidirectional+no_connect"))
    )
    (net (code "72") (name "unconnected-(U4-IO10-Pad18)") (class "Default")
      (node (ref "U4") (pin "18") (pinfunction "IO10_18") (pintype "bidirectional+no_connect"))
    )
    (net (code "73") (name "unconnected-(U4-IO11-Pad19)") (class "Default")
      (node (ref "U4") (pin "19") (pinfunction "IO11_19") (pintype "bidirectional+no_connect"))
    )
    (net (code "74") (name "unconnected-(U4-IO12-Pad20)") (class "Default")
      (node (ref "U4") (pin "20") (pinfunction "IO12_20") (pintype "bidirectional+no_connect"))
    )
    (net (code "75") (name "unconnected-(U4-IO15-Pad8)") (class "Default")
      (node (ref "U4") (pin "8") (pinfunction "IO15_8") (pintype "bidirectional+no_connect"))
    )
    (net (code "76") (name "unconnected-(U4-IO16-Pad9)") (class "Default")
      (node (ref "U4") (pin "9") (pinfunction "IO16_9") (pintype "bidirectional+no_connect"))
    )
    (net (code "77") (name "unconnected-(U4-IO17-Pad10)") (class "Default")
      (node (ref "U4") (pin "10") (pinfunction "IO17_10") (pintype "bidirectional+no_connect"))
    )
    (net (code "78") (name "unconnected-(U4-IO18-Pad11)") (class "Default")
      (node (ref "U4") (pin "11") (pinfunction "IO18_11") (pintype "bidirectional+no_connect"))
    )
    (net (code "79") (name "unconnected-(U4-IO19-Pad13)") (class "Default")
      (node (ref "U4") (pin "13") (pinfunction "IO19_13") (pintype "bidirectional+no_connect"))
    )
    (net (code "80") (name "unconnected-(U4-IO20-Pad14)") (class "Default")
      (node (ref "U4") (pin "14") (pinfunction "IO20_14") (pintype "bidirectional+no_connect"))
    )
    (net (code "81") (name "unconnected-(U4-IO21-Pad23)") (class "Default")
      (node (ref "U4") (pin "23") (pinfunction "IO21_23") (pintype "bidirectional+no_connect"))
    )
    (net (code "82") (name "unconnected-(U4-IO35-Pad28)") (class "Default")
      (node (ref "U4") (pin "28") (pinfunction "IO35_28") (pintype "bidirectional+no_connect"))
    )
    (net (code "83") (name "unconnected-(U4-IO36-Pad29)") (class "Default")
      (node (ref "U4") (pin "29") (pinfunction "IO36_29") (pintype "bidirectional+no_connect"))
    )
    (net (code "84") (name "unconnected-(U4-IO37-Pad30)") (class "Default")
      (node (ref "U4") (pin "30") (pinfunction "IO37_30") (pintype "bidirectional+no_connect"))
    )
    (net (code "85") (name "unconnected-(U4-IO38-Pad31)") (class "Default")
      (node (ref "U4") (pin "31") (pinfunction "IO38_31") (pintype "bidirectional+no_connect"))
    )
    (net (code "86") (name "unconnected-(U4-IO39-Pad32)") (class "Default")
      (node (ref "U4") (pin "32") (pinfunction "IO39_32") (pintype "bidirectional+no_connect"))
    )
    (net (code "87") (name "unconnected-(U4-IO40-Pad33)") (class "Default")
      (node (ref "U4") (pin "33") (pinfunction "IO40_33") (pintype "bidirectional+no_connect"))
    )
    (net (code "88") (name "unconnected-(U4-IO41-Pad34)") (class "Default")
      (node (ref "U4") (pin "34") (pinfunction "IO41_34") (pintype "bidirectional+no_connect"))
    )
    (net (code "89") (name "unconnected-(U4-IO42-Pad35)") (class "Default")
      (node (ref "U4") (pin "35") (pinfunction "IO42_35") (pintype "bidirectional+no_connect"))
    )
    (net (code "90") (name "unconnected-(U4-IO45-Pad26)") (class "Default")
      (node (ref "U4") (pin "26") (pinfunction "IO45_26") (pintype "bidirectional+no_connect"))
    )
    (net (code "91") (name "unconnected-(U4-IO46-Pad16)") (class "Default")
      (node (ref "U4") (pin "16") (pinfunction "IO46_16") (pintype "bidirectional+no_connect"))
    )
    (net (code "92") (name "unconnected-(U6A-SUSPEND-Pad12)") (class "Default")
      (node (ref "U6") (pin "12") (pinfunction "SUSPEND_12") (pintype "output+no_connect"))
    )
    (net (code "93") (name "unconnected-(U6A-~{CTS}-Pad23)") (class "Default")
      (node (ref "U6") (pin "23") (pinfunction "~{CTS}_23") (pintype "input+no_connect"))
    )
    (net (code "94") (name "unconnected-(U6A-~{DCD}-Pad1)") (class "Default")
      (node (ref "U6") (pin "1") (pinfunction "~{DCD}_1") (pintype "input+no_connect"))
    )
    (net (code "95") (name "unconnected-(U6A-~{DSR}-Pad27)") (class "Default")
      (node (ref "U6") (pin "27") (pinfunction "~{DSR}_27") (pintype "input+no_connect"))
    )
    (net (code "96") (name "unconnected-(U6A-~{RI}-Pad2)") (class "Default")
      (node (ref "U6") (pin "2") (pinfunction "~{RI}_2") (pintype "input+no_connect"))
    )
  )
)
